# Input.net
KiCad netlist of a schematic drawn in Altium Designer
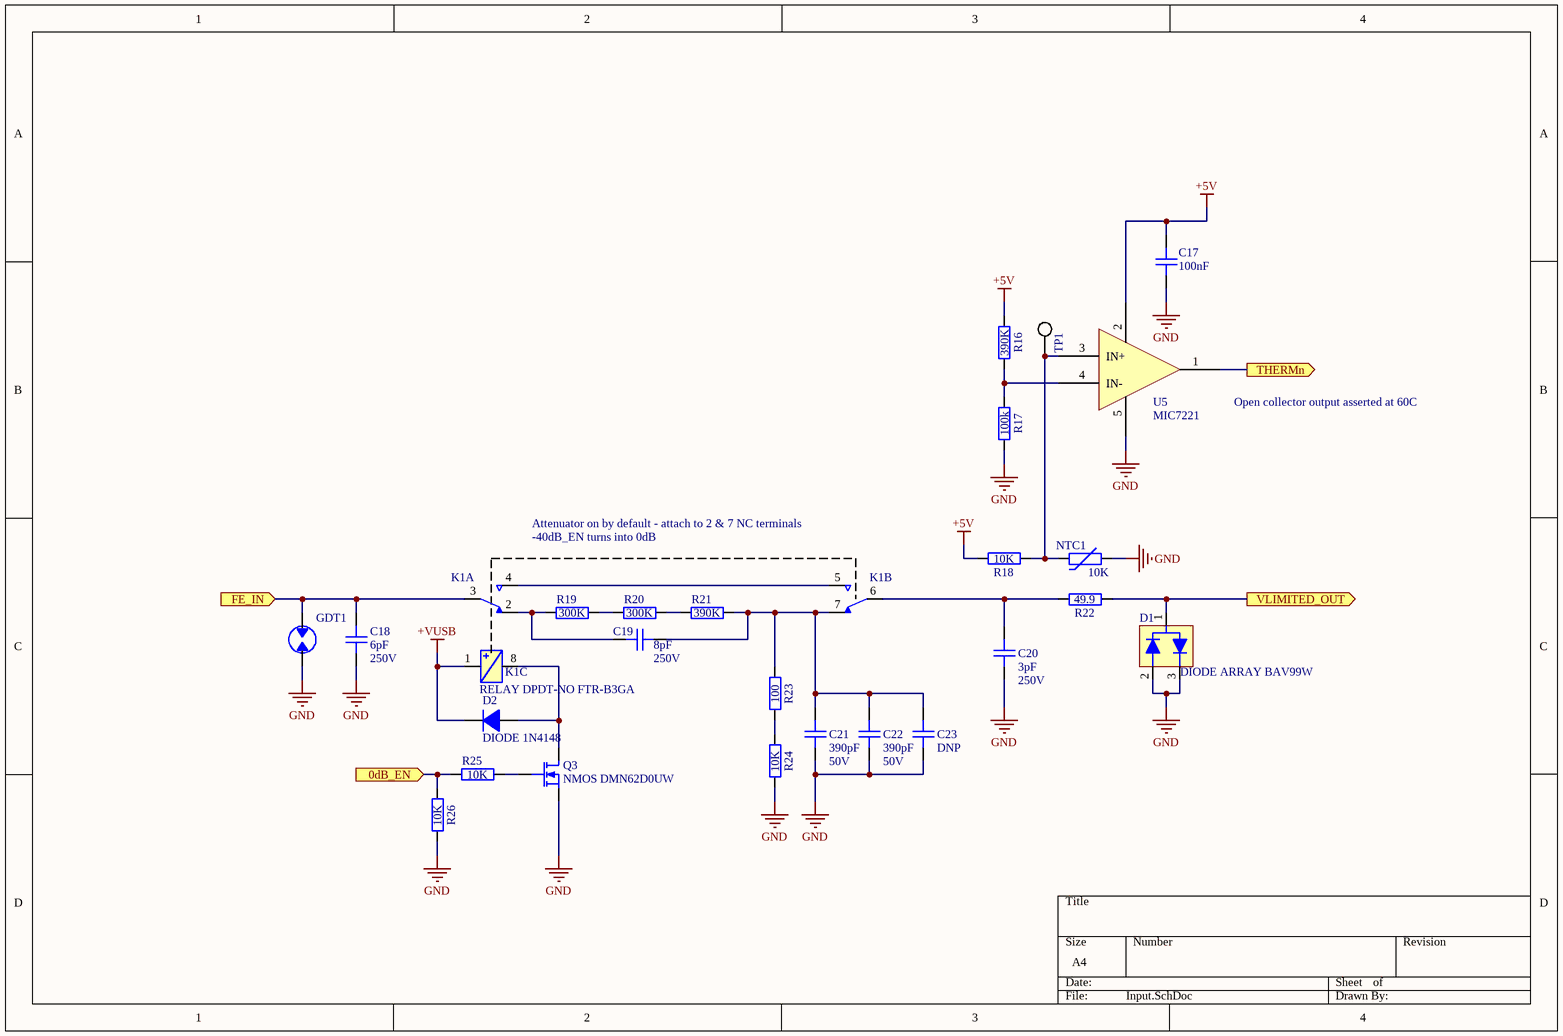
[diagram p0: Input.SchDoc]

(export (version "E")
  (design (tool "Eeschema 10.0.6"))
  (components
    (comp (ref "C17")
      (value "100nF")
      (footprint "GEN_C_0402")
      (fields (field (name "Comment") "CAP 100nF 16V X7R 0402"))
      (libsource (lib "DSO") (part "CAP 100nF 16V X7R 0402"))
    )
    (comp (ref "C18")
      (value "6pF")
      (footprint "GEN_C_0603")
      (fields (field (name "VOLTAGE RATING") "250V") (field (name "Comment") "CAP 6pF 250V C0G 0603"))
      (libsource (lib "DSO") (part "CAP 6pF 250V C0G 0603"))
    )
    (comp (ref "C19")
      (value "8pF")
      (footprint "GEN_C_0603")
      (fields (field (name "VOLTAGE RATING") "250V") (field (name "Comment") "CAP 8pF 250V C0G 0603"))
      (libsource (lib "DSO") (part "CAP 8pF 250V C0G 0603"))
    )
    (comp (ref "C20")
      (value "3pF")
      (footprint "GEN_C_0603")
      (fields (field (name "VOLTAGE RATING") "250V") (field (name "Comment") "CAP 3pF 250V C0G 0603"))
      (libsource (lib "DSO") (part "CAP 3pF 250V C0G 0603"))
    )
    (comp (ref "C21")
      (value "390pF")
      (footprint "GEN_C_0402")
      (fields (field (name "VOLTAGE RATING") "50V") (field (name "Comment") "CAP 390pF 50V C0G 0402"))
      (libsource (lib "DSO") (part "CAP 390pF 50V C0G 0402"))
    )
    (comp (ref "C22")
      (value "390pF")
      (footprint "GEN_C_0402")
      (fields (field (name "VOLTAGE RATING") "50V") (field (name "Comment") "CAP 390pF 50V C0G 0402"))
      (libsource (lib "DSO") (part "CAP 390pF 50V C0G 0402"))
    )
    (comp (ref "C23")
      (value "DNP")
      (footprint "GEN_C_0402")
      (fields (field (name "Comment") "CAP DNP 0402"))
      (libsource (lib "DSO") (part "CAP DNP 0402"))
    )
    (comp (ref "D1")
      (value "DIODE ARRAY BAV99W")
      (footprint "GEN_SOT_323")
      (libsource (lib "DSO") (part "DIODE ARRAY BAV99W"))
    )
    (comp (ref "D2")
      (value "DIODE 1N4148")
      (footprint "GEN_SOD_323")
      (libsource (lib "DSO") (part "DIODE 1N4148"))
    )
    (comp (ref "GDT1") (value "GDT 90V") (footprint "BOU_2051") (libsource (lib "DSO") (part "GDT 90V")))
    (comp (ref "K1")
      (value "RELAY DPDT-NO FTR-B3GA")
      (footprint "FUJ_FTR-B3GA")
      (libsource (lib "") (part "RELAY DPDT-NO FTR-B3GA_1"))
    )
    (comp (ref "NTC1")
      (value "10K")
      (footprint "GEN_R_0402")
      (fields (field (name "Comment") "NTC 10K 3900K 0402"))
      (libsource (lib "DSO") (part "NTC 10K 3900K 0402"))
    )
    (comp (ref "Q3")
      (value "NMOS DMN62D0UW")
      (footprint "GEN_SOT_323")
      (libsource (lib "DSO") (part "NMOS DMN62D0UW"))
    )
    (comp (ref "R16")
      (value "390K")
      (footprint "GEN_R_0402")
      (fields (field (name "TOLERANCE") "1%") (field (name "Comment") "RES 390K OHM 1% 1/10W 0402"))
      (libsource (lib "DSO") (part "RES 390K OHM 1% 1/10W 0402"))
    )
    (comp (ref "R17")
      (value "100k")
      (footprint "GEN_R_0402")
      (fields (field (name "TOLERANCE") "1%") (field (name "Comment") "RES 100K OHM 1% 1/10W 0402"))
      (libsource (lib "DSO") (part "RES 100K OHM 1% 1/10W 0402"))
    )
    (comp (ref "R18")
      (value "10K")
      (footprint "GEN_R_0402")
      (fields (field (name "TOLERANCE") "1%") (field (name "Comment") "RES 10K OHM 1% 1/10W 0402"))
      (libsource (lib "DSO") (part "RES 10K OHM 1% 1/10W 0402"))
    )
    (comp (ref "R19")
      (value "300K")
      (footprint "GEN_R_0402")
      (fields (field (name "TOLERANCE") "1%") (field (name "Comment") "RES 300K OHM 1% 1/10W 0402"))
      (libsource (lib "DSO") (part "RES 300K OHM 1% 1/10W 0402"))
    )
    (comp (ref "R20")
      (value "300K")
      (footprint "GEN_R_0402")
      (fields (field (name "TOLERANCE") "1%") (field (name "Comment") "RES 300K OHM 1% 1/10W 0402"))
      (libsource (lib "DSO") (part "RES 300K OHM 1% 1/10W 0402"))
    )
    (comp (ref "R21")
      (value "390K")
      (footprint "GEN_R_0402")
      (fields (field (name "TOLERANCE") "1%") (field (name "Comment") "RES 390K OHM 1% 1/10W 0402"))
      (libsource (lib "") (part "RES 390K OHM 1% 1/10W 0402_1"))
    )
    (comp (ref "R22")
      (value "49.9")
      (footprint "GEN_R_0402")
      (fields (field (name "TOLERANCE") "1%"))
      (libsource (lib "DSO") (part "RES 49.9 OHM 1% 1/10W 0402"))
    )
    (comp (ref "R23")
      (value "100")
      (footprint "GEN_R_0402")
      (fields (field (name "TOLERANCE") "1%") (field (name "Comment") "RES 100 OHM 1% 1/10W 0402"))
      (libsource (lib "DSO") (part "RES 100 OHM 1% 1/10W 0402"))
    )
    (comp (ref "R24")
      (value "10K")
      (footprint "GEN_R_0402")
      (fields (field (name "TOLERANCE") "1%") (field (name "Comment") "RES 10K OHM 1% 1/10W 0402"))
      (libsource (lib "") (part "RES 10K OHM 1% 1/10W 0402_1"))
    )
    (comp (ref "R25")
      (value "10K")
      (footprint "GEN_R_0402")
      (fields (field (name "TOLERANCE") "1%") (field (name "Comment") "RES 10K OHM 1% 1/10W 0402"))
      (libsource (lib "DSO") (part "RES 10K OHM 1% 1/10W 0402"))
    )
    (comp (ref "R26")
      (value "10K")
      (footprint "GEN_R_0402")
      (fields (field (name "TOLERANCE") "1%") (field (name "Comment") "RES 10K OHM 1% 1/10W 0402"))
      (libsource (lib "") (part "RES 10K OHM 1% 1/10W 0402_1"))
    )
    (comp (ref "TP1") (value "5019") (footprint "KEY_5019") (libsource (lib "DSO") (part "TP KEYSTONE 5019")))
    (comp (ref "U5")
      (value "MIC7221")
      (footprint "GEN_SOT23_5_950_2900X1600X1450")
      (libsource (lib "DSO") (part "IC COMP MIC7221YM5"))
    )
  )
  (nets
    (net (code "1") (name "+5V") (class "Default")
      (node (ref "C17") (pin "1") (pinfunction "1_1") (pintype "passive"))
      (node (ref "R16") (pin "1") (pinfunction "1_1") (pintype "passive"))
      (node (ref "R18") (pin "2") (pinfunction "2_2") (pintype "passive"))
      (node (ref "U5") (pin "2") (pinfunction "V+_2") (pintype "passive"))
    )
    (net (code "2") (name "+VUSB") (class "Default")
      (node (ref "D2") (pin "1") (pinfunction "K_1") (pintype "passive"))
      (node (ref "K1") (pin "1") (pinfunction "1_1") (pintype "passive"))
    )
    (net (code "3") (name "/0dB_EN") (class "Default")
      (node (ref "R25") (pin "2") (pinfunction "2_2") (pintype "passive"))
      (node (ref "R26") (pin "2") (pinfunction "2_2") (pintype "passive"))
    )
    (net (code "4") (name "/FE_IN") (class "Default")
      (node (ref "C18") (pin "2") (pinfunction "2_2") (pintype "passive"))
      (node (ref "GDT1") (pin "1") (pinfunction "1_1") (pintype "passive"))
      (node (ref "K1") (pin "3") (pinfunction "3_3") (pintype "passive"))
    )
    (net (code "5") (name "/THERMn") (class "Default")
      (node (ref "U5") (pin "1") (pinfunction "OUT_1") (pintype "open_collector"))
    )
    (net (code "6") (name "/VLIMITED_OUT") (class "Default")
      (node (ref "D1") (pin "1") (pintype "passive"))
      (node (ref "R22") (pin "2") (pinfunction "2_2") (pintype "passive"))
    )
    (net (code "7") (name "GND") (class "Default")
      (node (ref "C17") (pin "2") (pinfunction "2_2") (pintype "passive"))
      (node (ref "C18") (pin "1") (pinfunction "1_1") (pintype "passive"))
      (node (ref "C20") (pin "2") (pinfunction "2_2") (pintype "passive"))
      (node (ref "C21") (pin "1") (pinfunction "1_1") (pintype "passive"))
      (node (ref "C22") (pin "1") (pinfunction "1_1") (pintype "passive"))
      (node (ref "C23") (pin "1") (pinfunction "1_1") (pintype "passive"))
      (node (ref "D1") (pin "2") (pinfunction "2_2") (pintype "passive"))
      (node (ref "D1") (pin "3") (pinfunction "3_3") (pintype "passive"))
      (node (ref "GDT1") (pin "2") (pinfunction "2_2") (pintype "passive"))
      (node (ref "NTC1") (pin "2") (pinfunction "2_2") (pintype "passive"))
      (node (ref "Q3") (pin "3") (pinfunction "S_3") (pintype "passive"))
      (node (ref "R17") (pin "2") (pinfunction "2_2") (pintype "passive"))
      (node (ref "R24") (pin "1") (pinfunction "1_1") (pintype "passive"))
      (node (ref "R26") (pin "1") (pinfunction "1_1") (pintype "passive"))
      (node (ref "U5") (pin "5") (pinfunction "V-_5") (pintype "passive"))
    )
    (net (code "8") (name "Net-(C19-Pad1)") (class "Default")
      (node (ref "C19") (pin "1") (pinfunction "1_1") (pintype "passive"))
      (node (ref "C21") (pin "2") (pinfunction "2_2") (pintype "passive"))
      (node (ref "C22") (pin "2") (pinfunction "2_2") (pintype "passive"))
      (node (ref "C23") (pin "2") (pinfunction "2_2") (pintype "passive"))
      (node (ref "K1") (pin "7") (pinfunction "7_7") (pintype "passive"))
      (node (ref "R21") (pin "2") (pinfunction "2_2") (pintype "passive"))
      (node (ref "R23") (pin "2") (pinfunction "2_2") (pintype "passive"))
    )
    (net (code "9") (name "Net-(C19-Pad2)") (class "Default")
      (node (ref "C19") (pin "2") (pinfunction "2_2") (pintype "passive"))
      (node (ref "K1") (pin "2") (pinfunction "2_2") (pintype "passive"))
      (node (ref "R19") (pin "1") (pinfunction "1_1") (pintype "passive"))
    )
    (net (code "10") (name "Net-(C20-Pad1)") (class "Default")
      (node (ref "C20") (pin "1") (pinfunction "1_1") (pintype "passive"))
      (node (ref "K1") (pin "6") (pinfunction "6_6") (pintype "passive"))
      (node (ref "R22") (pin "1") (pinfunction "1_1") (pintype "passive"))
    )
    (net (code "11") (name "Net-(D2-A)") (class "Default")
      (node (ref "D2") (pin "2") (pinfunction "A_2") (pintype "passive"))
      (node (ref "K1") (pin "8") (pinfunction "8_8") (pintype "passive"))
      (node (ref "Q3") (pin "1") (pinfunction "D_1") (pintype "passive"))
    )
    (net (code "12") (name "Net-(K1-Pad4)") (class "Default")
      (node (ref "K1") (pin "4") (pinfunction "4_4") (pintype "passive"))
      (node (ref "K1") (pin "5") (pinfunction "5_5") (pintype "passive"))
    )
    (net (code "13") (name "Net-(Q3-G)") (class "Default")
      (node (ref "Q3") (pin "2") (pinfunction "G_2") (pintype "passive"))
      (node (ref "R25") (pin "1") (pinfunction "1_1") (pintype "passive"))
    )
    (net (code "14") (name "Net-(R19-Pad2)") (class "Default")
      (node (ref "R19") (pin "2") (pinfunction "2_2") (pintype "passive"))
      (node (ref "R20") (pin "1") (pinfunction "1_1") (pintype "passive"))
    )
    (net (code "15") (name "Net-(R20-Pad2)") (class "Default")
      (node (ref "R20") (pin "2") (pinfunction "2_2") (pintype "passive"))
      (node (ref "R21") (pin "1") (pinfunction "1_1") (pintype "passive"))
    )
    (net (code "16") (name "Net-(R23-Pad1)") (class "Default")
      (node (ref "R23") (pin "1") (pinfunction "1_1") (pintype "passive"))
      (node (ref "R24") (pin "2") (pinfunction "2_2") (pintype "passive"))
    )
    (net (code "17") (name "Net-(U5-IN+)") (class "Default")
      (node (ref "NTC1") (pin "1") (pinfunction "1_1") (pintype "passive"))
      (node (ref "R18") (pin "1") (pinfunction "1_1") (pintype "passive"))
      (node (ref "TP1") (pin "1") (pinfunction "1_1") (pintype "passive"))
      (node (ref "U5") (pin "3") (pinfunction "IN+_3") (pintype "passive"))
    )
    (net (code "18") (name "Net-(U5-IN-)") (class "Default")
      (node (ref "R16") (pin "2") (pinfunction "2_2") (pintype "passive"))
      (node (ref "R17") (pin "1") (pinfunction "1_1") (pintype "passive"))
      (node (ref "U5") (pin "4") (pinfunction "IN-_4") (pintype "passive"))
    )
  )
)
